# DSO_ADC.net
KiCad netlist of a schematic drawn in Altium Designer
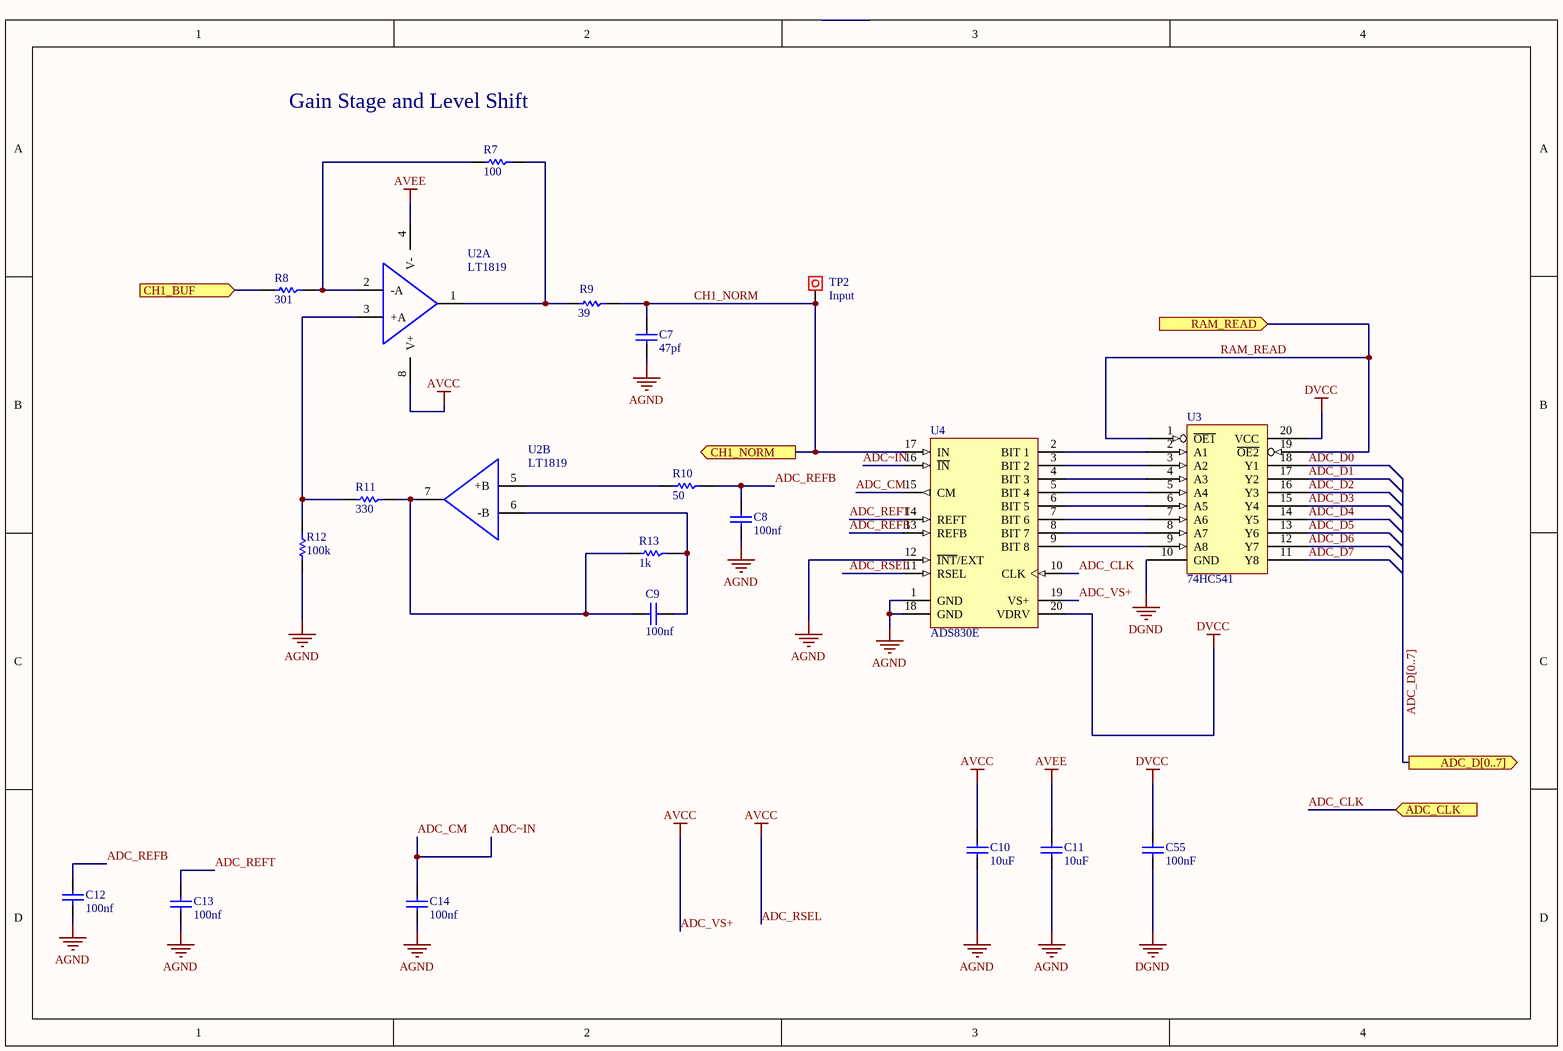
[diagram p0: DSO_ADC.SchDoc]

(export (version "E")
  (design (tool "Eeschema 10.0.6"))
  (components
    (comp (ref "C7")
      (value "47pf")
      (footprint "0805C")
      (description "Capacitor")
      (fields (field (name "REVIEWED BY") "RM - 2018/08/05"))
      (libsource (lib "DSO") (part "C"))
    )
    (comp (ref "C8")
      (value "100nf")
      (footprint "0805C")
      (description "Capacitor")
      (fields (field (name "REVIEWED BY") "RM - 2018/08/05"))
      (libsource (lib "DSO") (part "C"))
    )
    (comp (ref "C9")
      (value "100nf")
      (footprint "0805C")
      (description "Capacitor")
      (fields (field (name "REVIEWED BY") "RM - 2018/08/05"))
      (libsource (lib "DSO") (part "C"))
    )
    (comp (ref "C10")
      (value "10uF")
      (footprint "0805C")
      (description "Capacitor")
      (fields (field (name "REVIEWED BY") "RM - 2018/08/05"))
      (libsource (lib "DSO") (part "C"))
    )
    (comp (ref "C11")
      (value "10uF")
      (footprint "0805C")
      (description "Capacitor")
      (fields (field (name "REVIEWED BY") "RM - 2018/08/05"))
      (libsource (lib "DSO") (part "C"))
    )
    (comp (ref "C12")
      (value "100nf")
      (footprint "0805C")
      (description "Capacitor")
      (fields (field (name "REVIEWED BY") "RM - 2018/08/05"))
      (libsource (lib "DSO") (part "C"))
    )
    (comp (ref "C13")
      (value "100nf")
      (footprint "0805C")
      (description "Capacitor")
      (fields (field (name "REVIEWED BY") "RM - 2018/08/05"))
      (libsource (lib "DSO") (part "C"))
    )
    (comp (ref "C14")
      (value "100nf")
      (footprint "0805C")
      (description "Capacitor")
      (fields (field (name "REVIEWED BY") "RM - 2018/08/05"))
      (libsource (lib "DSO") (part "C"))
    )
    (comp (ref "C55")
      (value "100nF")
      (footprint "0805C")
      (description "Capacitor")
      (fields (field (name "REVIEWED BY") "RM - 2018/08/05"))
      (libsource (lib "DSO") (part "C"))
    )
    (comp (ref "R7")
      (value "100")
      (footprint "0805")
      (description "Resistor")
      (fields (field (name "REVIEWED BY") "RM - 2018/08/05"))
      (libsource (lib "DSO") (part "R"))
    )
    (comp (ref "R8")
      (value "301")
      (footprint "0805")
      (description "Resistor")
      (fields (field (name "REVIEWED BY") "RM - 2018/08/05"))
      (libsource (lib "DSO") (part "R"))
    )
    (comp (ref "R9")
      (value "39")
      (footprint "0805")
      (description "Resistor")
      (fields (field (name "REVIEWED BY") "RM - 2018/08/05"))
      (libsource (lib "DSO") (part "R"))
    )
    (comp (ref "R10")
      (value "50")
      (footprint "0805")
      (description "Resistor")
      (fields (field (name "REVIEWED BY") "RM - 2018/08/05"))
      (libsource (lib "DSO") (part "R"))
    )
    (comp (ref "R11")
      (value "330")
      (footprint "0805")
      (description "Resistor")
      (fields (field (name "REVIEWED BY") "RM - 2018/08/05"))
      (libsource (lib "DSO") (part "R"))
    )
    (comp (ref "R12")
      (value "100k")
      (footprint "0805")
      (description "Resistor")
      (fields (field (name "REVIEWED BY") "RM - 2018/08/05"))
      (libsource (lib "DSO") (part "R"))
    )
    (comp (ref "R13")
      (value "1k")
      (footprint "0805")
      (description "Resistor")
      (fields (field (name "REVIEWED BY") "RM - 2018/08/05"))
      (libsource (lib "DSO") (part "R"))
    )
    (comp (ref "TP2")
      (value "Input")
      (footprint "Testpoin")
      (description "Pad")
      (fields (field (name "Comment") "INPUT"))
      (libsource (lib "DSO") (part "Test Point"))
    )
    (comp (ref "U2")
      (value "LT1819")
      (footprint "MSOP-8")
      (description "OpAmp High Frequency Dual")
      (fields (field (name "REVIEWED BY") "RM - 2018/08/05"))
      (libsource (lib "DSO") (part "LT1819"))
    )
    (comp (ref "U3")
      (value "74HC541")
      (footprint "SOT163-1_N")
      (description "(ADV) Octal Buffer, Line Driver")
      (fields (field (name "REVIEWED BY") "RM - 2018/08/05"))
      (libsource (lib "DSO") (part "74HC541"))
    )
    (comp (ref "U4")
      (value "ADS830E")
      (footprint "TI-DBQ20_L")
      (fields (field (name "REVIEWED BY") "RM - 2018/08/05"))
      (libsource (lib "DSO") (part "ADS830E"))
    )
  )
  (nets
    (net (code "1") (name "/ADC_CLK") (class "Default")
      (node (ref "U4") (pin "10") (pinfunction "CLK_10") (pintype "input"))
    )
    (net (code "2") (name "/ADC_CM") (class "Default")
      (node (ref "C14") (pin "2") (pinfunction "2_2") (pintype "passive"))
      (node (ref "U4") (pin "15") (pinfunction "CM_15") (pintype "output"))
      (node (ref "U4") (pin "16") (pinfunction "~{IN}_16") (pintype "input"))
    )
    (net (code "3") (name "/ADC_D0") (class "Default")
      (node (ref "U3") (pin "18") (pinfunction "Y1_18") (pintype "tri_state"))
    )
    (net (code "4") (name "/ADC_D1") (class "Default")
      (node (ref "U3") (pin "17") (pinfunction "Y2_17") (pintype "tri_state"))
    )
    (net (code "5") (name "/ADC_D2") (class "Default")
      (node (ref "U3") (pin "16") (pinfunction "Y3_16") (pintype "tri_state"))
    )
    (net (code "6") (name "/ADC_D3") (class "Default")
      (node (ref "U3") (pin "15") (pinfunction "Y4_15") (pintype "tri_state"))
    )
    (net (code "7") (name "/ADC_D4") (class "Default")
      (node (ref "U3") (pin "14") (pinfunction "Y5_14") (pintype "tri_state"))
    )
    (net (code "8") (name "/ADC_D5") (class "Default")
      (node (ref "U3") (pin "13") (pinfunction "Y6_13") (pintype "tri_state"))
    )
    (net (code "9") (name "/ADC_D6") (class "Default")
      (node (ref "U3") (pin "12") (pinfunction "Y7_12") (pintype "tri_state"))
    )
    (net (code "10") (name "/ADC_D7") (class "Default")
      (node (ref "U3") (pin "11") (pinfunction "Y8_11") (pintype "tri_state"))
    )
    (net (code "12") (name "/ADC_REFB") (class "Default")
      (node (ref "C12") (pin "2") (pinfunction "2_2") (pintype "passive"))
      (node (ref "C8") (pin "2") (pinfunction "2_2") (pintype "passive"))
      (node (ref "R10") (pin "1") (pintype "passive"))
      (node (ref "U4") (pin "13") (pinfunction "REFB_13") (pintype "input"))
    )
    (net (code "13") (name "/ADC_REFT") (class "Default")
      (node (ref "C13") (pin "2") (pinfunction "2_2") (pintype "passive"))
      (node (ref "U4") (pin "14") (pinfunction "REFT_14") (pintype "input"))
    )
    (net (code "14") (name "/CH1_BUF") (class "Default") (node (ref "R8") (pin "2") (pintype "passive")))
    (net (code "15") (name "/CH1_NORM") (class "Default")
      (node (ref "C7") (pin "1") (pinfunction "1_1") (pintype "passive"))
      (node (ref "R9") (pin "1") (pintype "passive"))
      (node (ref "TP2") (pin "1") (pintype "passive"))
      (node (ref "U4") (pin "17") (pinfunction "IN_17") (pintype "input"))
    )
    (net (code "16") (name "/RAM_READ") (class "Default")
      (node (ref "U3") (pin "1") (pinfunction "~{OE1}_1") (pintype "input"))
      (node (ref "U3") (pin "19") (pinfunction "~{OE2}_19") (pintype "input"))
    )
    (net (code "17") (name "AGND") (class "Default")
      (node (ref "C10") (pin "2") (pinfunction "2_2") (pintype "passive"))
      (node (ref "C11") (pin "2") (pinfunction "2_2") (pintype "passive"))
      (node (ref "C12") (pin "1") (pinfunction "1_1") (pintype "passive"))
      (node (ref "C13") (pin "1") (pinfunction "1_1") (pintype "passive"))
      (node (ref "C14") (pin "1") (pinfunction "1_1") (pintype "passive"))
      (node (ref "C7") (pin "2") (pinfunction "2_2") (pintype "passive"))
      (node (ref "C8") (pin "1") (pinfunction "1_1") (pintype "passive"))
      (node (ref "R12") (pin "2") (pintype "passive"))
      (node (ref "U4") (pin "1") (pinfunction "GND_1") (pintype "power_in"))
      (node (ref "U4") (pin "12") (pinfunction "~{INT}/EXT_12") (pintype "input"))
      (node (ref "U4") (pin "18") (pinfunction "GND_18") (pintype "power_in"))
    )
    (net (code "18") (name "AVCC") (class "Default")
      (node (ref "C10") (pin "1") (pinfunction "1_1") (pintype "passive"))
      (node (ref "U2") (pin "8") (pinfunction "V+_8") (pintype "passive"))
      (node (ref "U4") (pin "11") (pinfunction "RSEL_11") (pintype "input"))
      (node (ref "U4") (pin "19") (pinfunction "VS+_19") (pintype "power_in"))
    )
    (net (code "19") (name "AVEE") (class "Default")
      (node (ref "C11") (pin "1") (pinfunction "1_1") (pintype "passive"))
      (node (ref "U2") (pin "4") (pinfunction "V-_4") (pintype "passive"))
    )
    (net (code "20") (name "DGND") (class "Default")
      (node (ref "C55") (pin "2") (pinfunction "2_2") (pintype "passive"))
      (node (ref "U3") (pin "10") (pinfunction "GND_10") (pintype "power_in"))
    )
    (net (code "21") (name "DVCC") (class "Default")
      (node (ref "C55") (pin "1") (pinfunction "1_1") (pintype "passive"))
      (node (ref "U3") (pin "20") (pinfunction "VCC_20") (pintype "power_in"))
      (node (ref "U4") (pin "20") (pinfunction "VDRV_20") (pintype "power_in"))
    )
    (net (code "22") (name "Net-(U2A-+A)") (class "Default")
      (node (ref "R11") (pin "2") (pintype "passive"))
      (node (ref "R12") (pin "1") (pintype "passive"))
      (node (ref "U2") (pin "3") (pinfunction "+A_3") (pintype "passive"))
    )
    (net (code "23") (name "Net-(U2A--A)") (class "Default")
      (node (ref "R7") (pin "2") (pintype "passive"))
      (node (ref "R8") (pin "1") (pintype "passive"))
      (node (ref "U2") (pin "2") (pinfunction "-A_2") (pintype "passive"))
    )
    (net (code "24") (name "Net-(U2A-OUTA)") (class "Default")
      (node (ref "R7") (pin "1") (pintype "passive"))
      (node (ref "R9") (pin "2") (pintype "passive"))
      (node (ref "U2") (pin "1") (pinfunction "OUTA_1") (pintype "passive"))
    )
    (net (code "25") (name "Net-(U2B-+B)") (class "Default")
      (node (ref "R10") (pin "2") (pintype "passive"))
      (node (ref "U2") (pin "5") (pinfunction "+B_5") (pintype "passive"))
    )
    (net (code "26") (name "Net-(U2B--B)") (class "Default")
      (node (ref "C9") (pin "2") (pinfunction "2_2") (pintype "passive"))
      (node (ref "R13") (pin "1") (pintype "passive"))
      (node (ref "U2") (pin "6") (pinfunction "-B_6") (pintype "passive"))
    )
    (net (code "27") (name "Net-(U2B-OUTB)") (class "Default")
      (node (ref "C9") (pin "1") (pinfunction "1_1") (pintype "passive"))
      (node (ref "R11") (pin "1") (pintype "passive"))
      (node (ref "R13") (pin "2") (pintype "passive"))
      (node (ref "U2") (pin "7") (pinfunction "OUTB_7") (pintype "passive"))
    )
    (net (code "28") (name "Net-(U3-A1)") (class "Default")
      (node (ref "U3") (pin "2") (pinfunction "A1_2") (pintype "input"))
      (node (ref "U4") (pin "2") (pinfunction "BIT_1_2") (pintype "tri_state"))
    )
    (net (code "29") (name "Net-(U3-A2)") (class "Default")
      (node (ref "U3") (pin "3") (pinfunction "A2_3") (pintype "input"))
      (node (ref "U4") (pin "3") (pinfunction "BIT_2_3") (pintype "tri_state"))
    )
    (net (code "30") (name "Net-(U3-A3)") (class "Default")
      (node (ref "U3") (pin "4") (pinfunction "A3_4") (pintype "input"))
      (node (ref "U4") (pin "4") (pinfunction "BIT_3_4") (pintype "tri_state"))
    )
    (net (code "31") (name "Net-(U3-A4)") (class "Default")
      (node (ref "U3") (pin "5") (pinfunction "A4_5") (pintype "input"))
      (node (ref "U4") (pin "5") (pinfunction "BIT_4_5") (pintype "tri_state"))
    )
    (net (code "32") (name "Net-(U3-A5)") (class "Default")
      (node (ref "U3") (pin "6") (pinfunction "A5_6") (pintype "input"))
      (node (ref "U4") (pin "6") (pinfunction "BIT_5_6") (pintype "tri_state"))
    )
    (net (code "33") (name "Net-(U3-A6)") (class "Default")
      (node (ref "U3") (pin "7") (pinfunction "A6_7") (pintype "input"))
      (node (ref "U4") (pin "7") (pinfunction "BIT_6_7") (pintype "tri_state"))
    )
    (net (code "34") (name "Net-(U3-A7)") (class "Default")
      (node (ref "U3") (pin "8") (pinfunction "A7_8") (pintype "input"))
      (node (ref "U4") (pin "8") (pinfunction "BIT_7_8") (pintype "tri_state"))
    )
    (net (code "35") (name "Net-(U3-A8)") (class "Default")
      (node (ref "U3") (pin "9") (pinfunction "A8_9") (pintype "input"))
      (node (ref "U4") (pin "9") (pinfunction "BIT_8_9") (pintype "tri_state"))
    )
  )
)
